# ESP8266_1BTN.net
KiCad netlist of a schematic drawn in EAGLE
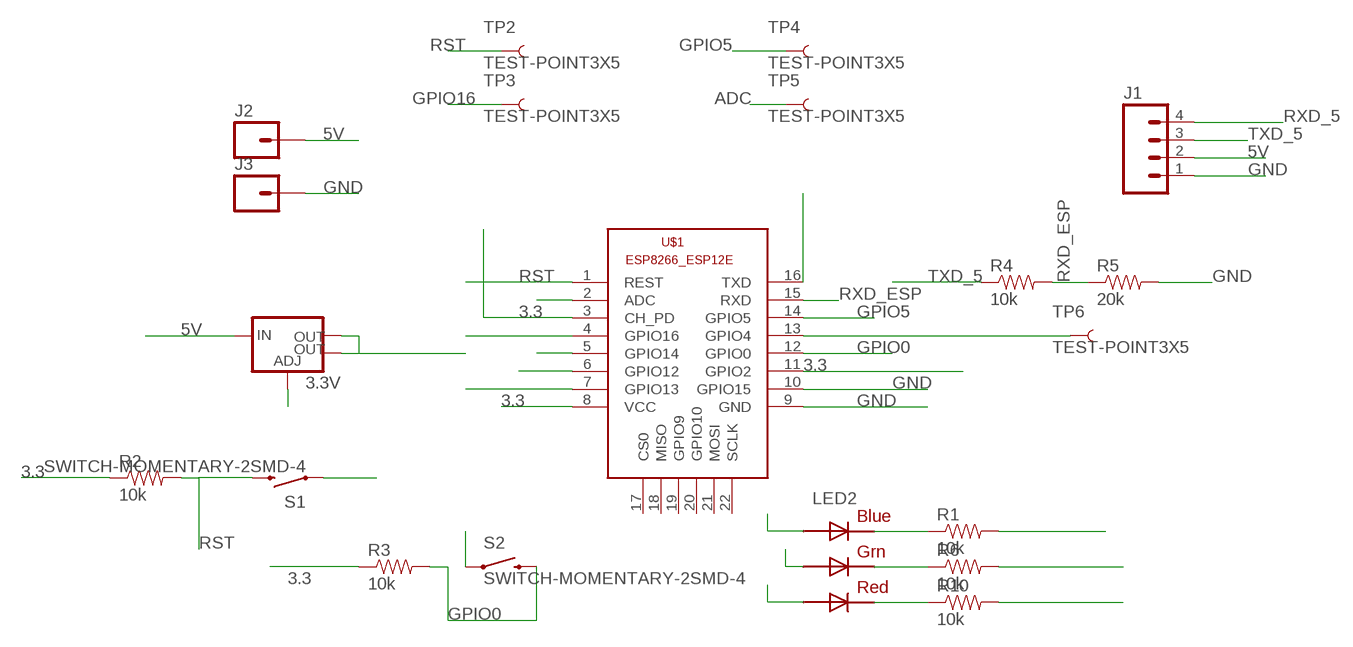
[diagram p0: schematic, sheet 1]

(export (version "E")
  (design (tool "Eeschema 10.0.6"))
  (components
    (comp (ref "3.3V")
      (value "V_REG_LM1117SOT223")
      (footprint "eagle-import:SOT223")
      (libsource (lib "eagle-import") (part "V_REG_LM1117SOT223"))
    )
    (comp (ref "J1")
      (value "M04SMD")
      (footprint "eagle-import:1X04-SMD")
      (libsource (lib "eagle-import") (part "M04SMD"))
    )
    (comp (ref "J2")
      (value "M01SMD")
      (footprint "eagle-import:LUXEON-PAD")
      (libsource (lib "eagle-import") (part "M01SMD"))
    )
    (comp (ref "J3")
      (value "M01SMD")
      (footprint "eagle-import:LUXEON-PAD")
      (libsource (lib "eagle-import") (part "M01SMD"))
    )
    (comp (ref "LED2")
      (value "RGBLED5050")
      (footprint "eagle-import:RGBLED5050")
      (libsource (lib "eagle-import") (part "RGBLED5050"))
    )
    (comp (ref "R1")
      (value "10k")
      (footprint "eagle-import:1206")
      (libsource (lib "eagle-import") (part "RESISTOR1206"))
    )
    (comp (ref "R2")
      (value "10k")
      (footprint "eagle-import:1206")
      (libsource (lib "eagle-import") (part "RESISTOR1206"))
    )
    (comp (ref "R3")
      (value "10k")
      (footprint "eagle-import:1206")
      (libsource (lib "eagle-import") (part "RESISTOR1206"))
    )
    (comp (ref "R4")
      (value "10k")
      (footprint "eagle-import:1206")
      (libsource (lib "eagle-import") (part "RESISTOR1206"))
    )
    (comp (ref "R5")
      (value "20k")
      (footprint "eagle-import:1206")
      (libsource (lib "eagle-import") (part "RESISTOR1206"))
    )
    (comp (ref "R6")
      (value "10k")
      (footprint "eagle-import:1206")
      (libsource (lib "eagle-import") (part "RESISTOR1206"))
    )
    (comp (ref "R10")
      (value "10k")
      (footprint "eagle-import:1206")
      (libsource (lib "eagle-import") (part "RESISTOR1206"))
    )
    (comp (ref "S1")
      (value "SWITCH-MOMENTARY-2SMD-4")
      (footprint "eagle-import:TACTILE_SWITCH_TALL")
      (libsource (lib "eagle-import") (part "SWITCH-MOMENTARY-2SMD-4"))
    )
    (comp (ref "S2")
      (value "SWITCH-MOMENTARY-2SMD-4")
      (footprint "eagle-import:TACTILE_SWITCH_TALL")
      (libsource (lib "eagle-import") (part "SWITCH-MOMENTARY-2SMD-4"))
    )
    (comp (ref "TP2")
      (value "TEST-POINT3X5")
      (footprint "eagle-import:PAD.03X.05")
      (libsource (lib "eagle-import") (part "TEST-POINT3X5"))
    )
    (comp (ref "TP3")
      (value "TEST-POINT3X5")
      (footprint "eagle-import:PAD.03X.05")
      (libsource (lib "eagle-import") (part "TEST-POINT3X5"))
    )
    (comp (ref "TP4")
      (value "TEST-POINT3X5")
      (footprint "eagle-import:PAD.03X.05")
      (libsource (lib "eagle-import") (part "TEST-POINT3X5"))
    )
    (comp (ref "TP5")
      (value "TEST-POINT3X5")
      (footprint "eagle-import:PAD.03X.05")
      (libsource (lib "eagle-import") (part "TEST-POINT3X5"))
    )
    (comp (ref "TP6")
      (value "TEST-POINT3X5")
      (footprint "eagle-import:PAD.03X.05")
      (libsource (lib "eagle-import") (part "TEST-POINT3X5"))
    )
    (comp (ref "U$1")
      (value "ESP8266-12EESP8266-ESP12E")
      (footprint "eagle-import:ESP8266-ESP12E")
      (libsource (lib "eagle-import") (part "ESP8266-12EESP8266-ESP12E"))
    )
  )
  (nets
    (net (code "1") (name "/3.3") (class "Default")
      (node (ref "3.3V") (pin "2") (pinfunction "OUT_2") (pintype "output"))
      (node (ref "3.3V") (pin "4") (pinfunction "OUT_4") (pintype "output"))
      (node (ref "R2") (pin "1") (pinfunction "1_1") (pintype "passive"))
      (node (ref "R3") (pin "1") (pinfunction "1_1") (pintype "passive"))
      (node (ref "U$1") (pin "11") (pinfunction "GPIO2_11") (pintype "bidirectional"))
      (node (ref "U$1") (pin "3") (pinfunction "CH_PD_3") (pintype "bidirectional"))
      (node (ref "U$1") (pin "8") (pinfunction "VCC_8") (pintype "bidirectional"))
    )
    (net (code "2") (name "/5V") (class "Default")
      (node (ref "3.3V") (pin "3") (pinfunction "IN_3") (pintype "input"))
      (node (ref "J1") (pin "2") (pinfunction "2_2") (pintype "passive"))
      (node (ref "J2") (pin "P$1") (pinfunction "1_P$1") (pintype "passive"))
    )
    (net (code "3") (name "/ADC") (class "Default")
      (node (ref "TP5") (pin "P$1") (pinfunction "1_P$1") (pintype "bidirectional"))
      (node (ref "U$1") (pin "2") (pinfunction "ADC_2") (pintype "bidirectional"))
    )
    (net (code "4") (name "/BLUE") (class "Default")
      (node (ref "LED2") (pin "3") (pinfunction "BLUE_A_3") (pintype "bidirectional"))
      (node (ref "U$1") (pin "5") (pinfunction "GPIO14_5") (pintype "bidirectional"))
    )
    (net (code "5") (name "/GND") (class "Default")
      (node (ref "3.3V") (pin "1") (pinfunction "ADJ_1") (pintype "input"))
      (node (ref "J1") (pin "1") (pinfunction "1_1") (pintype "passive"))
      (node (ref "J3") (pin "P$1") (pinfunction "1_P$1") (pintype "passive"))
      (node (ref "R1") (pin "2") (pinfunction "2_2") (pintype "passive"))
      (node (ref "R10") (pin "2") (pinfunction "2_2") (pintype "passive"))
      (node (ref "R5") (pin "2") (pinfunction "2_2") (pintype "passive"))
      (node (ref "R6") (pin "2") (pinfunction "2_2") (pintype "passive"))
      (node (ref "S1") (pin "A2") (pinfunction "1_A2") (pintype "passive"))
      (node (ref "S2") (pin "A2") (pinfunction "1_A2") (pintype "passive"))
      (node (ref "U$1") (pin "10") (pinfunction "GPIO15_10") (pintype "bidirectional"))
      (node (ref "U$1") (pin "9") (pinfunction "GND_9") (pintype "bidirectional"))
    )
    (net (code "6") (name "/GPIO0") (class "Default")
      (node (ref "R3") (pin "2") (pinfunction "2_2") (pintype "passive"))
      (node (ref "S2") (pin "B2") (pinfunction "2_B2") (pintype "passive"))
      (node (ref "U$1") (pin "12") (pinfunction "GPIO0_12") (pintype "bidirectional"))
    )
    (net (code "7") (name "/GPIO5") (class "Default")
      (node (ref "TP4") (pin "P$1") (pinfunction "1_P$1") (pintype "bidirectional"))
      (node (ref "U$1") (pin "14") (pinfunction "GPIO5_14") (pintype "bidirectional"))
    )
    (net (code "8") (name "/GPIO16") (class "Default")
      (node (ref "TP3") (pin "P$1") (pinfunction "1_P$1") (pintype "bidirectional"))
      (node (ref "U$1") (pin "4") (pinfunction "GPIO16_4") (pintype "bidirectional"))
    )
    (net (code "9") (name "/GREEN") (class "Default")
      (node (ref "LED2") (pin "1") (pinfunction "GREEN_A_1") (pintype "bidirectional"))
      (node (ref "U$1") (pin "7") (pinfunction "GPIO13_7") (pintype "bidirectional"))
    )
    (net (code "10") (name "/RED") (class "Default")
      (node (ref "LED2") (pin "2") (pinfunction "RED_A_2") (pintype "bidirectional"))
      (node (ref "U$1") (pin "6") (pinfunction "GPIO12_6") (pintype "bidirectional"))
    )
    (net (code "11") (name "/RST") (class "Default")
      (node (ref "R2") (pin "2") (pinfunction "2_2") (pintype "passive"))
      (node (ref "S1") (pin "B2") (pinfunction "2_B2") (pintype "passive"))
      (node (ref "TP2") (pin "P$1") (pinfunction "1_P$1") (pintype "bidirectional"))
      (node (ref "U$1") (pin "1") (pinfunction "REST_1") (pintype "bidirectional"))
    )
    (net (code "12") (name "/RXD_5") (class "Default")
      (node (ref "J1") (pin "4") (pinfunction "4_4") (pintype "passive"))
      (node (ref "U$1") (pin "16") (pinfunction "TXD_16") (pintype "bidirectional"))
    )
    (net (code "13") (name "/RXD_ESP") (class "Default")
      (node (ref "R4") (pin "2") (pinfunction "2_2") (pintype "passive"))
      (node (ref "R5") (pin "1") (pinfunction "1_1") (pintype "passive"))
      (node (ref "U$1") (pin "15") (pinfunction "RXD_15") (pintype "bidirectional"))
    )
    (net (code "14") (name "/TXD_5") (class "Default")
      (node (ref "J1") (pin "3") (pinfunction "3_3") (pintype "passive"))
      (node (ref "R4") (pin "1") (pinfunction "1_1") (pintype "passive"))
    )
    (net (code "15") (name "Net-(LED2-BLUE_C)") (class "Default")
      (node (ref "LED2") (pin "4") (pinfunction "BLUE_C_4") (pintype "bidirectional"))
      (node (ref "R1") (pin "1") (pinfunction "1_1") (pintype "passive"))
    )
    (net (code "16") (name "Net-(LED2-GREEN_C)") (class "Default")
      (node (ref "LED2") (pin "6") (pinfunction "GREEN_C_6") (pintype "bidirectional"))
      (node (ref "R6") (pin "1") (pinfunction "1_1") (pintype "passive"))
    )
    (net (code "17") (name "Net-(LED2-RED_C)") (class "Default")
      (node (ref "LED2") (pin "5") (pinfunction "RED_C_5") (pintype "bidirectional"))
      (node (ref "R10") (pin "1") (pinfunction "1_1") (pintype "passive"))
    )
    (net (code "18") (name "Net-(TP6-1)") (class "Default")
      (node (ref "TP6") (pin "P$1") (pinfunction "1_P$1") (pintype "bidirectional"))
      (node (ref "U$1") (pin "13") (pinfunction "GPIO4_13") (pintype "bidirectional"))
    )
    (net (code "19") (name "unconnected-(U$1-CS0-Pad17)") (class "Default")
      (node (ref "U$1") (pin "17") (pinfunction "CS0_17") (pintype "bidirectional"))
    )
    (net (code "20") (name "unconnected-(U$1-GPIO9-Pad19)") (class "Default")
      (node (ref "U$1") (pin "19") (pinfunction "GPIO9_19") (pintype "bidirectional"))
    )
    (net (code "21") (name "unconnected-(U$1-GPIO10-Pad20)") (class "Default")
      (node (ref "U$1") (pin "20") (pinfunction "GPIO10_20") (pintype "bidirectional"))
    )
    (net (code "22") (name "unconnected-(U$1-MISO-Pad18)") (class "Default")
      (node (ref "U$1") (pin "18") (pinfunction "MISO_18") (pintype "bidirectional"))
    )
    (net (code "23") (name "unconnected-(U$1-MOSI-Pad21)") (class "Default")
      (node (ref "U$1") (pin "21") (pinfunction "MOSI_21") (pintype "bidirectional"))
    )
    (net (code "24") (name "unconnected-(U$1-SCLK-Pad22)") (class "Default")
      (node (ref "U$1") (pin "22") (pinfunction "SCLK_22") (pintype "bidirectional"))
    )
  )
)
